# 2_bootleg-2-matrix.net
KiCad netlist of a schematic drawn in Altium Designer
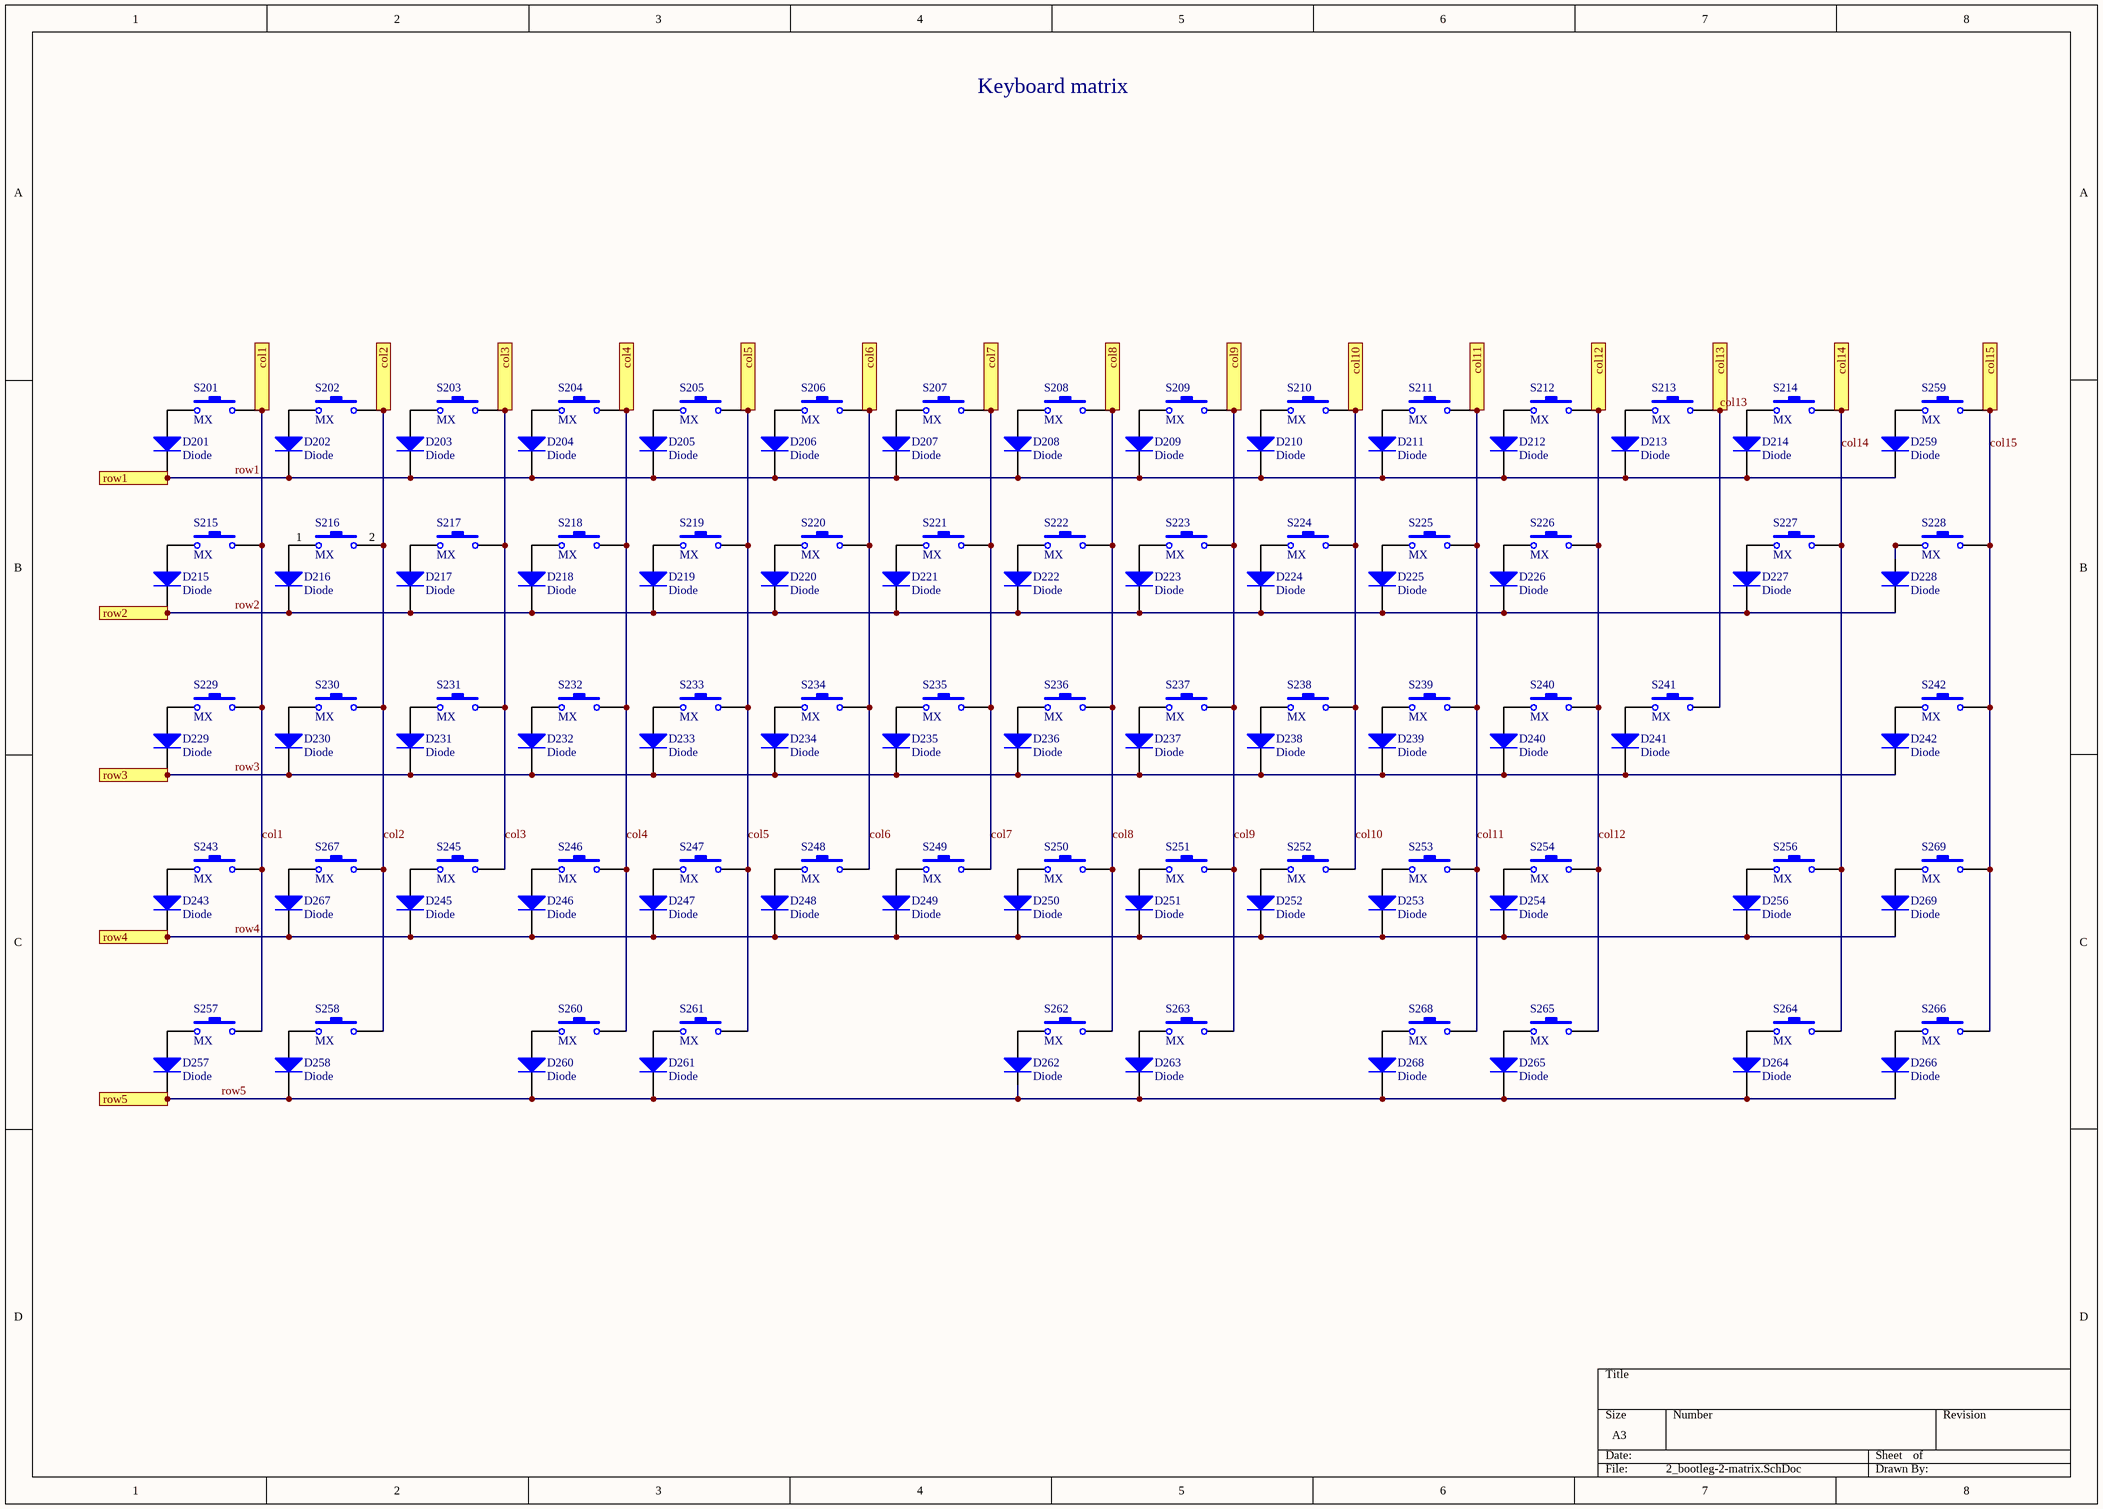
[diagram p0: 2_bootleg-2-matrix.SchDoc]

(export (version "E")
  (design (tool "Eeschema 10.0.6"))
  (components
    (comp (ref "D201")
      (value "Diode")
      (footprint "SOD-123")
      (description "Default Diode")
      (fields (field (name "MFG") "Bourns Inc.") (field (name "LCSC PART #") "C109002"))
      (libsource (lib "Miscellaneous Devices") (part "Diode"))
    )
    (comp (ref "D202")
      (value "Diode")
      (footprint "SOD-123")
      (description "Default Diode")
      (fields (field (name "MFG") "Bourns Inc.") (field (name "LCSC PART #") "C109002"))
      (libsource (lib "Miscellaneous Devices") (part "Diode"))
    )
    (comp (ref "D203")
      (value "Diode")
      (footprint "SOD-123")
      (description "Default Diode")
      (fields (field (name "MFG") "Bourns Inc.") (field (name "LCSC PART #") "C109002"))
      (libsource (lib "Miscellaneous Devices") (part "Diode"))
    )
    (comp (ref "D204")
      (value "Diode")
      (footprint "SOD-123")
      (description "Default Diode")
      (fields (field (name "MFG") "Bourns Inc.") (field (name "LCSC PART #") "C109002"))
      (libsource (lib "Miscellaneous Devices") (part "Diode"))
    )
    (comp (ref "D205")
      (value "Diode")
      (footprint "SOD-123")
      (description "Default Diode")
      (fields (field (name "MFG") "Bourns Inc.") (field (name "LCSC PART #") "C109002"))
      (libsource (lib "Miscellaneous Devices") (part "Diode"))
    )
    (comp (ref "D206")
      (value "Diode")
      (footprint "SOD-123")
      (description "Default Diode")
      (fields (field (name "MFG") "Bourns Inc.") (field (name "LCSC PART #") "C109002"))
      (libsource (lib "Miscellaneous Devices") (part "Diode"))
    )
    (comp (ref "D207")
      (value "Diode")
      (footprint "SOD-123")
      (description "Default Diode")
      (fields (field (name "MFG") "Bourns Inc.") (field (name "LCSC PART #") "C109002"))
      (libsource (lib "Miscellaneous Devices") (part "Diode"))
    )
    (comp (ref "D208")
      (value "Diode")
      (footprint "SOD-123")
      (description "Default Diode")
      (fields (field (name "MFG") "Bourns Inc.") (field (name "LCSC PART #") "C109002"))
      (libsource (lib "Miscellaneous Devices") (part "Diode"))
    )
    (comp (ref "D209")
      (value "Diode")
      (footprint "SOD-123")
      (description "Default Diode")
      (fields (field (name "MFG") "Bourns Inc.") (field (name "LCSC PART #") "C109002"))
      (libsource (lib "Miscellaneous Devices") (part "Diode"))
    )
    (comp (ref "D210")
      (value "Diode")
      (footprint "SOD-123")
      (description "Default Diode")
      (fields (field (name "MFG") "Bourns Inc.") (field (name "LCSC PART #") "C109002"))
      (libsource (lib "Miscellaneous Devices") (part "Diode"))
    )
    (comp (ref "D211")
      (value "Diode")
      (footprint "SOD-123")
      (description "Default Diode")
      (fields (field (name "MFG") "Bourns Inc.") (field (name "LCSC PART #") "C109002"))
      (libsource (lib "Miscellaneous Devices") (part "Diode"))
    )
    (comp (ref "D212")
      (value "Diode")
      (footprint "SOD-123")
      (description "Default Diode")
      (fields (field (name "MFG") "Bourns Inc.") (field (name "LCSC PART #") "C109002"))
      (libsource (lib "Miscellaneous Devices") (part "Diode"))
    )
    (comp (ref "D213")
      (value "Diode")
      (footprint "SOD-123")
      (description "Default Diode")
      (fields (field (name "MFG") "Bourns Inc.") (field (name "LCSC PART #") "C109002"))
      (libsource (lib "Miscellaneous Devices") (part "Diode"))
    )
    (comp (ref "D214")
      (value "Diode")
      (footprint "SOD-123")
      (description "Default Diode")
      (fields (field (name "MFG") "Bourns Inc.") (field (name "LCSC PART #") "C109002"))
      (libsource (lib "Miscellaneous Devices") (part "Diode"))
    )
    (comp (ref "D215")
      (value "Diode")
      (footprint "SOD-123")
      (description "Default Diode")
      (fields (field (name "MFG") "Bourns Inc.") (field (name "LCSC PART #") "C109002"))
      (libsource (lib "Miscellaneous Devices") (part "Diode"))
    )
    (comp (ref "D216")
      (value "Diode")
      (footprint "SOD-123")
      (description "Default Diode")
      (fields (field (name "MFG") "Bourns Inc.") (field (name "LCSC PART #") "C109002"))
      (libsource (lib "Miscellaneous Devices") (part "Diode"))
    )
    (comp (ref "D217")
      (value "Diode")
      (footprint "SOD-123")
      (description "Default Diode")
      (fields (field (name "MFG") "Bourns Inc.") (field (name "LCSC PART #") "C109002"))
      (libsource (lib "Miscellaneous Devices") (part "Diode"))
    )
    (comp (ref "D218")
      (value "Diode")
      (footprint "SOD-123")
      (description "Default Diode")
      (fields (field (name "MFG") "Bourns Inc.") (field (name "LCSC PART #") "C109002"))
      (libsource (lib "Miscellaneous Devices") (part "Diode"))
    )
    (comp (ref "D219")
      (value "Diode")
      (footprint "SOD-123")
      (description "Default Diode")
      (fields (field (name "MFG") "Bourns Inc.") (field (name "LCSC PART #") "C109002"))
      (libsource (lib "Miscellaneous Devices") (part "Diode"))
    )
    (comp (ref "D220")
      (value "Diode")
      (footprint "SOD-123")
      (description "Default Diode")
      (fields (field (name "MFG") "Bourns Inc.") (field (name "LCSC PART #") "C109002"))
      (libsource (lib "Miscellaneous Devices") (part "Diode"))
    )
    (comp (ref "D221")
      (value "Diode")
      (footprint "SOD-123")
      (description "Default Diode")
      (fields (field (name "MFG") "Bourns Inc.") (field (name "LCSC PART #") "C109002"))
      (libsource (lib "Miscellaneous Devices") (part "Diode"))
    )
    (comp (ref "D222")
      (value "Diode")
      (footprint "SOD-123")
      (description "Default Diode")
      (fields (field (name "MFG") "Bourns Inc.") (field (name "LCSC PART #") "C109002"))
      (libsource (lib "Miscellaneous Devices") (part "Diode"))
    )
    (comp (ref "D223")
      (value "Diode")
      (footprint "SOD-123")
      (description "Default Diode")
      (fields (field (name "MFG") "Bourns Inc.") (field (name "LCSC PART #") "C109002"))
      (libsource (lib "Miscellaneous Devices") (part "Diode"))
    )
    (comp (ref "D224")
      (value "Diode")
      (footprint "SOD-123")
      (description "Default Diode")
      (fields (field (name "MFG") "Bourns Inc.") (field (name "LCSC PART #") "C109002"))
      (libsource (lib "Miscellaneous Devices") (part "Diode"))
    )
    (comp (ref "D225")
      (value "Diode")
      (footprint "SOD-123")
      (description "Default Diode")
      (fields (field (name "MFG") "Bourns Inc.") (field (name "LCSC PART #") "C109002"))
      (libsource (lib "Miscellaneous Devices") (part "Diode"))
    )
    (comp (ref "D226")
      (value "Diode")
      (footprint "SOD-123")
      (description "Default Diode")
      (fields (field (name "MFG") "Bourns Inc.") (field (name "LCSC PART #") "C109002"))
      (libsource (lib "Miscellaneous Devices") (part "Diode"))
    )
    (comp (ref "D227")
      (value "Diode")
      (footprint "SOD-123")
      (description "Default Diode")
      (fields (field (name "MFG") "Bourns Inc.") (field (name "LCSC PART #") "C109002"))
      (libsource (lib "Miscellaneous Devices") (part "Diode"))
    )
    (comp (ref "D228")
      (value "Diode")
      (footprint "SOD-123")
      (description "Default Diode")
      (fields (field (name "MFG") "Bourns Inc.") (field (name "LCSC PART #") "C109002"))
      (libsource (lib "Miscellaneous Devices") (part "Diode"))
    )
    (comp (ref "D229")
      (value "Diode")
      (footprint "SOD-123")
      (description "Default Diode")
      (fields (field (name "MFG") "Bourns Inc.") (field (name "LCSC PART #") "C109002"))
      (libsource (lib "Miscellaneous Devices") (part "Diode"))
    )
    (comp (ref "D230")
      (value "Diode")
      (footprint "SOD-123")
      (description "Default Diode")
      (fields (field (name "MFG") "Bourns Inc.") (field (name "LCSC PART #") "C109002"))
      (libsource (lib "Miscellaneous Devices") (part "Diode"))
    )
    (comp (ref "D231")
      (value "Diode")
      (footprint "SOD-123")
      (description "Default Diode")
      (fields (field (name "MFG") "Bourns Inc.") (field (name "LCSC PART #") "C109002"))
      (libsource (lib "Miscellaneous Devices") (part "Diode"))
    )
    (comp (ref "D232")
      (value "Diode")
      (footprint "SOD-123")
      (description "Default Diode")
      (fields (field (name "MFG") "Bourns Inc.") (field (name "LCSC PART #") "C109002"))
      (libsource (lib "Miscellaneous Devices") (part "Diode"))
    )
    (comp (ref "D233")
      (value "Diode")
      (footprint "SOD-123")
      (description "Default Diode")
      (fields (field (name "MFG") "Bourns Inc.") (field (name "LCSC PART #") "C109002"))
      (libsource (lib "Miscellaneous Devices") (part "Diode"))
    )
    (comp (ref "D234")
      (value "Diode")
      (footprint "SOD-123")
      (description "Default Diode")
      (fields (field (name "MFG") "Bourns Inc.") (field (name "LCSC PART #") "C109002"))
      (libsource (lib "Miscellaneous Devices") (part "Diode"))
    )
    (comp (ref "D235")
      (value "Diode")
      (footprint "SOD-123")
      (description "Default Diode")
      (fields (field (name "MFG") "Bourns Inc.") (field (name "LCSC PART #") "C109002"))
      (libsource (lib "Miscellaneous Devices") (part "Diode"))
    )
    (comp (ref "D236")
      (value "Diode")
      (footprint "SOD-123")
      (description "Default Diode")
      (fields (field (name "MFG") "Bourns Inc.") (field (name "LCSC PART #") "C109002"))
      (libsource (lib "Miscellaneous Devices") (part "Diode"))
    )
    (comp (ref "D237")
      (value "Diode")
      (footprint "SOD-123")
      (description "Default Diode")
      (fields (field (name "MFG") "Bourns Inc.") (field (name "LCSC PART #") "C109002"))
      (libsource (lib "Miscellaneous Devices") (part "Diode"))
    )
    (comp (ref "D238")
      (value "Diode")
      (footprint "SOD-123")
      (description "Default Diode")
      (fields (field (name "MFG") "Bourns Inc.") (field (name "LCSC PART #") "C109002"))
      (libsource (lib "Miscellaneous Devices") (part "Diode"))
    )
    (comp (ref "D239")
      (value "Diode")
      (footprint "SOD-123")
      (description "Default Diode")
      (fields (field (name "MFG") "Bourns Inc.") (field (name "LCSC PART #") "C109002"))
      (libsource (lib "Miscellaneous Devices") (part "Diode"))
    )
    (comp (ref "D240")
      (value "Diode")
      (footprint "SOD-123")
      (description "Default Diode")
      (fields (field (name "MFG") "Bourns Inc.") (field (name "LCSC PART #") "C109002"))
      (libsource (lib "Miscellaneous Devices") (part "Diode"))
    )
    (comp (ref "D241")
      (value "Diode")
      (footprint "SOD-123")
      (description "Default Diode")
      (fields (field (name "MFG") "Bourns Inc.") (field (name "LCSC PART #") "C109002"))
      (libsource (lib "Miscellaneous Devices") (part "Diode"))
    )
    (comp (ref "D242")
      (value "Diode")
      (footprint "SOD-123")
      (description "Default Diode")
      (fields (field (name "MFG") "Bourns Inc.") (field (name "LCSC PART #") "C109002"))
      (libsource (lib "Miscellaneous Devices") (part "Diode"))
    )
    (comp (ref "D243")
      (value "Diode")
      (footprint "SOD-123")
      (description "Default Diode")
      (fields (field (name "MFG") "Bourns Inc.") (field (name "LCSC PART #") "C109002"))
      (libsource (lib "Miscellaneous Devices") (part "Diode"))
    )
    (comp (ref "D245")
      (value "Diode")
      (footprint "SOD-123")
      (description "Default Diode")
      (fields (field (name "MFG") "Bourns Inc.") (field (name "LCSC PART #") "C109002"))
      (libsource (lib "Miscellaneous Devices") (part "Diode"))
    )
    (comp (ref "D246")
      (value "Diode")
      (footprint "SOD-123")
      (description "Default Diode")
      (fields (field (name "MFG") "Bourns Inc.") (field (name "LCSC PART #") "C109002"))
      (libsource (lib "Miscellaneous Devices") (part "Diode"))
    )
    (comp (ref "D247")
      (value "Diode")
      (footprint "SOD-123")
      (description "Default Diode")
      (fields (field (name "MFG") "Bourns Inc.") (field (name "LCSC PART #") "C109002"))
      (libsource (lib "Miscellaneous Devices") (part "Diode"))
    )
    (comp (ref "D248")
      (value "Diode")
      (footprint "SOD-123")
      (description "Default Diode")
      (fields (field (name "MFG") "Bourns Inc.") (field (name "LCSC PART #") "C109002"))
      (libsource (lib "Miscellaneous Devices") (part "Diode"))
    )
    (comp (ref "D249")
      (value "Diode")
      (footprint "SOD-123")
      (description "Default Diode")
      (fields (field (name "MFG") "Bourns Inc.") (field (name "LCSC PART #") "C109002"))
      (libsource (lib "Miscellaneous Devices") (part "Diode"))
    )
    (comp (ref "D250")
      (value "Diode")
      (footprint "SOD-123")
      (description "Default Diode")
      (fields (field (name "MFG") "Bourns Inc.") (field (name "LCSC PART #") "C109002"))
      (libsource (lib "Miscellaneous Devices") (part "Diode"))
    )
    (comp (ref "D251")
      (value "Diode")
      (footprint "SOD-123")
      (description "Default Diode")
      (fields (field (name "MFG") "Bourns Inc.") (field (name "LCSC PART #") "C109002"))
      (libsource (lib "Miscellaneous Devices") (part "Diode"))
    )
    (comp (ref "D252")
      (value "Diode")
      (footprint "SOD-123")
      (description "Default Diode")
      (fields (field (name "MFG") "Bourns Inc.") (field (name "LCSC PART #") "C109002"))
      (libsource (lib "Miscellaneous Devices") (part "Diode"))
    )
    (comp (ref "D253")
      (value "Diode")
      (footprint "SOD-123")
      (description "Default Diode")
      (fields (field (name "MFG") "Bourns Inc.") (field (name "LCSC PART #") "C109002"))
      (libsource (lib "Miscellaneous Devices") (part "Diode"))
    )
    (comp (ref "D254")
      (value "Diode")
      (footprint "SOD-123")
      (description "Default Diode")
      (fields (field (name "MFG") "Bourns Inc.") (field (name "LCSC PART #") "C109002"))
      (libsource (lib "Miscellaneous Devices") (part "Diode"))
    )
    (comp (ref "D256")
      (value "Diode")
      (footprint "SOD-123")
      (description "Default Diode")
      (fields (field (name "MFG") "Bourns Inc.") (field (name "LCSC PART #") "C109002"))
      (libsource (lib "Miscellaneous Devices") (part "Diode"))
    )
    (comp (ref "D257")
      (value "Diode")
      (footprint "SOD-123")
      (description "Default Diode")
      (fields (field (name "MFG") "Bourns Inc.") (field (name "LCSC PART #") "C109002"))
      (libsource (lib "Miscellaneous Devices") (part "Diode"))
    )
    (comp (ref "D258")
      (value "Diode")
      (footprint "SOD-123")
      (description "Default Diode")
      (fields (field (name "MFG") "Bourns Inc.") (field (name "LCSC PART #") "C109002"))
      (libsource (lib "Miscellaneous Devices") (part "Diode"))
    )
    (comp (ref "D259")
      (value "Diode")
      (footprint "SOD-123")
      (description "Default Diode")
      (fields (field (name "MFG") "Bourns Inc.") (field (name "LCSC PART #") "C109002"))
      (libsource (lib "Miscellaneous Devices") (part "Diode"))
    )
    (comp (ref "D260")
      (value "Diode")
      (footprint "SOD-123")
      (description "Default Diode")
      (fields (field (name "MFG") "Bourns Inc.") (field (name "LCSC PART #") "C109002"))
      (libsource (lib "Miscellaneous Devices") (part "Diode"))
    )
    (comp (ref "D261")
      (value "Diode")
      (footprint "SOD-123")
      (description "Default Diode")
      (fields (field (name "MFG") "Bourns Inc.") (field (name "LCSC PART #") "C109002"))
      (libsource (lib "Miscellaneous Devices") (part "Diode"))
    )
    (comp (ref "D262")
      (value "Diode")
      (footprint "SOD-123")
      (description "Default Diode")
      (fields (field (name "MFG") "Bourns Inc.") (field (name "LCSC PART #") "C109002"))
      (libsource (lib "Miscellaneous Devices") (part "Diode"))
    )
    (comp (ref "D263")
      (value "Diode")
      (footprint "SOD-123")
      (description "Default Diode")
      (fields (field (name "MFG") "Bourns Inc.") (field (name "LCSC PART #") "C109002"))
      (libsource (lib "Miscellaneous Devices") (part "Diode"))
    )
    (comp (ref "D264")
      (value "Diode")
      (footprint "SOD-123")
      (description "Default Diode")
      (fields (field (name "MFG") "Bourns Inc.") (field (name "LCSC PART #") "C109002"))
      (libsource (lib "Miscellaneous Devices") (part "Diode"))
    )
    (comp (ref "D265")
      (value "Diode")
      (footprint "SOD-123")
      (description "Default Diode")
      (fields (field (name "MFG") "Bourns Inc.") (field (name "LCSC PART #") "C109002"))
      (libsource (lib "Miscellaneous Devices") (part "Diode"))
    )
    (comp (ref "D266")
      (value "Diode")
      (footprint "SOD-123")
      (description "Default Diode")
      (fields (field (name "MFG") "Bourns Inc.") (field (name "LCSC PART #") "C109002"))
      (libsource (lib "Miscellaneous Devices") (part "Diode"))
    )
    (comp (ref "D267")
      (value "Diode")
      (footprint "SOD-123")
      (description "Default Diode")
      (fields (field (name "MFG") "Bourns Inc.") (field (name "LCSC PART #") "C109002"))
      (libsource (lib "Miscellaneous Devices") (part "Diode"))
    )
    (comp (ref "D268")
      (value "Diode")
      (footprint "SOD-123")
      (description "Default Diode")
      (fields (field (name "MFG") "Bourns Inc.") (field (name "LCSC PART #") "C109002"))
      (libsource (lib "Miscellaneous Devices") (part "Diode"))
    )
    (comp (ref "D269")
      (value "Diode")
      (footprint "SOD-123")
      (description "Default Diode")
      (fields (field (name "MFG") "Bourns Inc.") (field (name "LCSC PART #") "C109002"))
      (libsource (lib "Miscellaneous Devices") (part "Diode"))
    )
    (comp (ref "S201")
      (value "MX")
      (footprint "Alps-switch - switched pol")
      (description "Switch")
      (libsource (lib "Miscellaneous Devices") (part "SW-PB"))
    )
    (comp (ref "S202")
      (value "MX")
      (footprint "Alps-switch - switched pol")
      (description "Switch")
      (libsource (lib "Miscellaneous Devices") (part "SW-PB"))
    )
    (comp (ref "S203")
      (value "MX")
      (footprint "Alps-switch - switched pol")
      (description "Switch")
      (libsource (lib "Miscellaneous Devices") (part "SW-PB"))
    )
    (comp (ref "S204")
      (value "MX")
      (footprint "Alps-switch - switched pol")
      (description "Switch")
      (libsource (lib "Miscellaneous Devices") (part "SW-PB"))
    )
    (comp (ref "S205")
      (value "MX")
      (footprint "Alps-switch - switched pol")
      (description "Switch")
      (libsource (lib "Miscellaneous Devices") (part "SW-PB"))
    )
    (comp (ref "S206")
      (value "MX")
      (footprint "Alps-switch - switched pol")
      (description "Switch")
      (libsource (lib "Miscellaneous Devices") (part "SW-PB"))
    )
    (comp (ref "S207")
      (value "MX")
      (footprint "Alps-switch - switched pol")
      (description "Switch")
      (libsource (lib "Miscellaneous Devices") (part "SW-PB"))
    )
    (comp (ref "S208")
      (value "MX")
      (footprint "Alps-switch - switched pol")
      (description "Switch")
      (libsource (lib "Miscellaneous Devices") (part "SW-PB"))
    )
    (comp (ref "S209")
      (value "MX")
      (footprint "Alps-switch - switched pol")
      (description "Switch")
      (libsource (lib "Miscellaneous Devices") (part "SW-PB"))
    )
    (comp (ref "S210")
      (value "MX")
      (footprint "Alps-switch - switched pol")
      (description "Switch")
      (libsource (lib "Miscellaneous Devices") (part "SW-PB"))
    )
    (comp (ref "S211")
      (value "MX")
      (footprint "Alps-switch - switched pol")
      (description "Switch")
      (libsource (lib "Miscellaneous Devices") (part "SW-PB"))
    )
    (comp (ref "S212")
      (value "MX")
      (footprint "Alps-switch - switched pol")
      (description "Switch")
      (libsource (lib "Miscellaneous Devices") (part "SW-PB"))
    )
    (comp (ref "S213")
      (value "MX")
      (footprint "Alps-switch - switched pol")
      (description "Switch")
      (libsource (lib "Miscellaneous Devices") (part "SW-PB"))
    )
    (comp (ref "S214")
      (value "MX")
      (footprint "Alps-switch - switched pol")
      (description "Switch")
      (libsource (lib "Miscellaneous Devices") (part "SW-PB"))
    )
    (comp (ref "S215")
      (value "MX")
      (footprint "ALPS-switch - 1.5U")
      (description "TAB")
      (libsource (lib "Miscellaneous Devices") (part "SW-PB"))
    )
    (comp (ref "S216")
      (value "MX")
      (footprint "Alps-switch - switched pol")
      (description "Switch")
      (libsource (lib "") (part "SW-PB_1"))
    )
    (comp (ref "S217")
      (value "MX")
      (footprint "Alps-switch - switched pol")
      (description "Switch")
      (libsource (lib "Miscellaneous Devices") (part "SW-PB"))
    )
    (comp (ref "S218")
      (value "MX")
      (footprint "Alps-switch - switched pol")
      (description "Switch")
      (libsource (lib "Miscellaneous Devices") (part "SW-PB"))
    )
    (comp (ref "S219")
      (value "MX")
      (footprint "Alps-switch - switched pol")
      (description "Switch")
      (libsource (lib "Miscellaneous Devices") (part "SW-PB"))
    )
    (comp (ref "S220")
      (value "MX")
      (footprint "Alps-switch - switched pol")
      (description "Switch")
      (libsource (lib "Miscellaneous Devices") (part "SW-PB"))
    )
    (comp (ref "S221")
      (value "MX")
      (footprint "Alps-switch - switched pol")
      (description "Switch")
      (libsource (lib "Miscellaneous Devices") (part "SW-PB"))
    )
    (comp (ref "S222")
      (value "MX")
      (footprint "Alps-switch - switched pol")
      (description "Switch")
      (libsource (lib "Miscellaneous Devices") (part "SW-PB"))
    )
    (comp (ref "S223")
      (value "MX")
      (footprint "Alps-switch - switched pol")
      (description "Switch")
      (libsource (lib "Miscellaneous Devices") (part "SW-PB"))
    )
    (comp (ref "S224")
      (value "MX")
      (footprint "Alps-switch - switched pol")
      (description "Switch")
      (libsource (lib "Miscellaneous Devices") (part "SW-PB"))
    )
    (comp (ref "S225")
      (value "MX")
      (footprint "Alps-switch - switched pol")
      (description "Switch")
      (libsource (lib "Miscellaneous Devices") (part "SW-PB"))
    )
    (comp (ref "S226")
      (value "MX")
      (footprint "Alps-switch")
      (description "Switch")
      (libsource (lib "Miscellaneous Devices") (part "SW-PB"))
    )
    (comp (ref "S227")
      (value "MX")
      (footprint "Alps-switch - switched pol")
      (description "Switch")
      (libsource (lib "Miscellaneous Devices") (part "SW-PB"))
    )
    (comp (ref "S228")
      (value "MX")
      (footprint "ALPS-switch - 1.5U")
      (description "Switch")
      (libsource (lib "Miscellaneous Devices") (part "SW-PB"))
    )
    (comp (ref "S229")
      (value "MX")
      (footprint "ALPS-switch - CAPS")
      (description "Switch")
      (libsource (lib "Miscellaneous Devices") (part "SW-PB"))
    )
    (comp (ref "S230")
      (value "MX")
      (footprint "Alps-switch - switched pol")
      (description "Switch")
      (libsource (lib "Miscellaneous Devices") (part "SW-PB"))
    )
    (comp (ref "S231")
      (value "MX")
      (footprint "Alps-switch - switched pol")
      (description "Switch")
      (libsource (lib "Miscellaneous Devices") (part "SW-PB"))
    )
    (comp (ref "S232")
      (value "MX")
      (footprint "Alps-switch - switched pol")
      (description "Switch")
      (libsource (lib "Miscellaneous Devices") (part "SW-PB"))
    )
    (comp (ref "S233")
      (value "MX")
      (footprint "Alps-switch - switched pol")
      (description "Switch")
      (libsource (lib "Miscellaneous Devices") (part "SW-PB"))
    )
    (comp (ref "S234")
      (value "MX")
      (footprint "Alps-switch - switched pol")
      (description "Switch")
      (libsource (lib "Miscellaneous Devices") (part "SW-PB"))
    )
    (comp (ref "S235")
      (value "MX")
      (footprint "Alps-switch - switched pol")
      (description "Switch")
      (libsource (lib "Miscellaneous Devices") (part "SW-PB"))
    )
    (comp (ref "S236")
      (value "MX")
      (footprint "Alps-switch - switched pol")
      (description "Switch")
      (libsource (lib "Miscellaneous Devices") (part "SW-PB"))
    )
    (comp (ref "S237")
      (value "MX")
      (footprint "Alps-switch - switched pol")
      (description "Switch")
      (libsource (lib "Miscellaneous Devices") (part "SW-PB"))
    )
    (comp (ref "S238")
      (value "MX")
      (footprint "Alps-switch - switched pol")
      (description "Switch")
      (libsource (lib "Miscellaneous Devices") (part "SW-PB"))
    )
    (comp (ref "S239")
      (value "MX")
      (footprint "Alps-switch")
      (description "Switch")
      (libsource (lib "Miscellaneous Devices") (part "SW-PB"))
    )
    (comp (ref "S240")
      (value "MX")
      (footprint "Alps-switch - switched pol")
      (description "Switch")
      (libsource (lib "Miscellaneous Devices") (part "SW-PB"))
    )
    (comp (ref "S241")
      (value "MX")
      (footprint "Alps-switch")
      (description "Switch")
      (libsource (lib "Miscellaneous Devices") (part "SW-PB"))
    )
    (comp (ref "S242")
      (value "MX")
      (footprint "ALPS-switch - Enter")
      (description "Switch")
      (libsource (lib "Miscellaneous Devices") (part "SW-PB"))
    )
    (comp (ref "S243")
      (value "MX")
      (footprint "ALPS-switch - Left shift v2")
      (description "Switch")
      (libsource (lib "Miscellaneous Devices") (part "SW-PB"))
    )
    (comp (ref "S245")
      (value "MX")
      (footprint "Alps-switch - switched pol")
      (description "Switch")
      (libsource (lib "Miscellaneous Devices") (part "SW-PB"))
    )
    (comp (ref "S246")
      (value "MX")
      (footprint "Alps-switch - switched pol")
      (description "Switch")
      (libsource (lib "Miscellaneous Devices") (part "SW-PB"))
    )
    (comp (ref "S247")
      (value "MX")
      (footprint "Alps-switch - switched pol")
      (description "Switch")
      (libsource (lib "Miscellaneous Devices") (part "SW-PB"))
    )
    (comp (ref "S248")
      (value "MX")
      (footprint "Alps-switch - switched pol")
      (description "Switch")
      (libsource (lib "Miscellaneous Devices") (part "SW-PB"))
    )
    (comp (ref "S249")
      (value "MX")
      (footprint "Alps-switch - switched pol")
      (description "Switch")
      (libsource (lib "Miscellaneous Devices") (part "SW-PB"))
    )
    (comp (ref "S250")
      (value "MX")
      (footprint "Alps-switch - switched pol")
      (description "Switch")
      (libsource (lib "Miscellaneous Devices") (part "SW-PB"))
    )
    (comp (ref "S251")
      (value "MX")
      (footprint "Alps-switch - switched pol")
      (description "Switch")
      (libsource (lib "Miscellaneous Devices") (part "SW-PB"))
    )
    (comp (ref "S252")
      (value "MX")
      (footprint "Alps-switch - switched pol")
      (description "Switch")
      (libsource (lib "Miscellaneous Devices") (part "SW-PB"))
    )
    (comp (ref "S253")
      (value "MX")
      (footprint "Alps-switch - switched pol")
      (description "Switch")
      (libsource (lib "Miscellaneous Devices") (part "SW-PB"))
    )
    (comp (ref "S254")
      (value "MX")
      (footprint "Alps-switch - switched pol")
      (description "Switch")
      (libsource (lib "Miscellaneous Devices") (part "SW-PB"))
    )
    (comp (ref "S256")
      (value "MX")
      (footprint "ALPS-switch - right shift - stabs")
      (description "Switch")
      (libsource (lib "Miscellaneous Devices") (part "SW-PB"))
    )
    (comp (ref "S257")
      (value "MX")
      (footprint "ALPS-switch - 1.5u MOD-L")
      (description "Switch")
      (libsource (lib "Miscellaneous Devices") (part "SW-PB"))
    )
    (comp (ref "S258")
      (value "MX")
      (footprint "ALPS-switch - L_WIN - AEKISO60")
      (description "Switch")
      (libsource (lib "Miscellaneous Devices") (part "SW-PB"))
    )
    (comp (ref "S259")
      (value "MX")
      (footprint "ALPS-switch - backspace")
      (description "Switch")
      (libsource (lib "Miscellaneous Devices") (part "SW-PB"))
    )
    (comp (ref "S260")
      (value "MX")
      (footprint "ALPS-switch - L_alt - V2")
      (description "Switch")
      (libsource (lib "Miscellaneous Devices") (part "SW-PB"))
    )
    (comp (ref "S261")
      (value "MX")
      (footprint "ALPS-SWITCH - L SPLIT SPACE_V2")
      (description "Switch")
      (libsource (lib "Miscellaneous Devices") (part "SW-PB"))
    )
    (comp (ref "S262")
      (value "MX")
      (footprint "ALPS-switch - Space_V3")
      (description "Switch")
      (libsource (lib "Miscellaneous Devices") (part "SW-PB"))
    )
    (comp (ref "S263")
      (value "MX")
      (footprint "ALPS-SWITCH - R SPLIT SPACE_V2")
      (description "Switch")
      (libsource (lib "Miscellaneous Devices") (part "SW-PB"))
    )
    (comp (ref "S264")
      (value "MX")
      (footprint "ALPS-switch - R_WIN - AEKISO60")
      (description "Switch")
      (libsource (lib "Miscellaneous Devices") (part "SW-PB"))
    )
    (comp (ref "S265")
      (value "MX")
      (footprint "ALPS-switch - R_alt - V2")
      (description "Switch")
      (libsource (lib "Miscellaneous Devices") (part "SW-PB"))
    )
    (comp (ref "S266")
      (value "MX")
      (footprint "ALPS-switch - 1.5u MOD-R")
      (description "Switch")
      (libsource (lib "Miscellaneous Devices") (part "SW-PB"))
    )
    (comp (ref "S267")
      (value "MX")
      (footprint "Alps-switch - switched pol")
      (description "Switch")
      (libsource (lib "Miscellaneous Devices") (part "SW-PB"))
    )
    (comp (ref "S268")
      (value "MX")
      (footprint "Alps-switch - switched pol")
      (description "Switch")
      (libsource (lib "Miscellaneous Devices") (part "SW-PB"))
    )
    (comp (ref "S269")
      (value "MX")
      (footprint "Alps-switch")
      (description "Switch")
      (libsource (lib "Miscellaneous Devices") (part "SW-PB"))
    )
  )
  (nets
    (net (code "1") (name "/col1") (class "Default")
      (node (ref "S201") (pin "2") (pinfunction "2_2") (pintype "passive"))
      (node (ref "S215") (pin "2") (pinfunction "2_2") (pintype "passive"))
      (node (ref "S229") (pin "2") (pinfunction "2_2") (pintype "passive"))
      (node (ref "S243") (pin "1") (pinfunction "1_1") (pintype "passive"))
      (node (ref "S257") (pin "1") (pinfunction "1_1") (pintype "passive"))
    )
    (net (code "2") (name "/col2") (class "Default")
      (node (ref "S202") (pin "2") (pinfunction "2_2") (pintype "passive"))
      (node (ref "S216") (pin "2") (pinfunction "2_2") (pintype "passive"))
      (node (ref "S230") (pin "2") (pinfunction "2_2") (pintype "passive"))
      (node (ref "S258") (pin "2") (pinfunction "2_2") (pintype "passive"))
      (node (ref "S267") (pin "2") (pinfunction "2_2") (pintype "passive"))
    )
    (net (code "3") (name "/col3") (class "Default")
      (node (ref "S203") (pin "2") (pinfunction "2_2") (pintype "passive"))
      (node (ref "S217") (pin "2") (pinfunction "2_2") (pintype "passive"))
      (node (ref "S231") (pin "2") (pinfunction "2_2") (pintype "passive"))
      (node (ref "S245") (pin "2") (pinfunction "2_2") (pintype "passive"))
    )
    (net (code "4") (name "/col4") (class "Default")
      (node (ref "S204") (pin "2") (pinfunction "2_2") (pintype "passive"))
      (node (ref "S218") (pin "2") (pinfunction "2_2") (pintype "passive"))
      (node (ref "S232") (pin "2") (pinfunction "2_2") (pintype "passive"))
      (node (ref "S246") (pin "2") (pinfunction "2_2") (pintype "passive"))
      (node (ref "S260") (pin "2") (pinfunction "2_2") (pintype "passive"))
    )
    (net (code "5") (name "/col5") (class "Default")
      (node (ref "S205") (pin "2") (pinfunction "2_2") (pintype "passive"))
      (node (ref "S219") (pin "2") (pinfunction "2_2") (pintype "passive"))
      (node (ref "S233") (pin "2") (pinfunction "2_2") (pintype "passive"))
      (node (ref "S247") (pin "2") (pinfunction "2_2") (pintype "passive"))
      (node (ref "S261") (pin "2") (pinfunction "2_2") (pintype "passive"))
    )
    (net (code "6") (name "/col6") (class "Default")
      (node (ref "S206") (pin "2") (pinfunction "2_2") (pintype "passive"))
      (node (ref "S220") (pin "2") (pinfunction "2_2") (pintype "passive"))
      (node (ref "S234") (pin "2") (pinfunction "2_2") (pintype "passive"))
      (node (ref "S248") (pin "2") (pinfunction "2_2") (pintype "passive"))
    )
    (net (code "7") (name "/col7") (class "Default")
      (node (ref "S207") (pin "2") (pinfunction "2_2") (pintype "passive"))
      (node (ref "S221") (pin "2") (pinfunction "2_2") (pintype "passive"))
      (node (ref "S235") (pin "2") (pinfunction "2_2") (pintype "passive"))
      (node (ref "S249") (pin "2") (pinfunction "2_2") (pintype "passive"))
    )
    (net (code "8") (name "/col8") (class "Default")
      (node (ref "S208") (pin "2") (pinfunction "2_2") (pintype "passive"))
      (node (ref "S222") (pin "2") (pinfunction "2_2") (pintype "passive"))
      (node (ref "S236") (pin "2") (pinfunction "2_2") (pintype "passive"))
      (node (ref "S250") (pin "2") (pinfunction "2_2") (pintype "passive"))
      (node (ref "S262") (pin "2") (pinfunction "2_2") (pintype "passive"))
    )
    (net (code "9") (name "/col9") (class "Default")
      (node (ref "S209") (pin "2") (pinfunction "2_2") (pintype "passive"))
      (node (ref "S223") (pin "2") (pinfunction "2_2") (pintype "passive"))
      (node (ref "S237") (pin "2") (pinfunction "2_2") (pintype "passive"))
      (node (ref "S251") (pin "2") (pinfunction "2_2") (pintype "passive"))
      (node (ref "S263") (pin "2") (pinfunction "2_2") (pintype "passive"))
    )
    (net (code "10") (name "/col10") (class "Default")
      (node (ref "S210") (pin "2") (pinfunction "2_2") (pintype "passive"))
      (node (ref "S224") (pin "2") (pinfunction "2_2") (pintype "passive"))
      (node (ref "S238") (pin "2") (pinfunction "2_2") (pintype "passive"))
      (node (ref "S252") (pin "2") (pinfunction "2_2") (pintype "passive"))
    )
    (net (code "11") (name "/col11") (class "Default")
      (node (ref "S211") (pin "2") (pinfunction "2_2") (pintype "passive"))
      (node (ref "S225") (pin "2") (pinfunction "2_2") (pintype "passive"))
      (node (ref "S239") (pin "2") (pinfunction "2_2") (pintype "passive"))
      (node (ref "S253") (pin "2") (pinfunction "2_2") (pintype "passive"))
      (node (ref "S268") (pin "1") (pinfunction "1_1") (pintype "passive"))
    )
    (net (code "12") (name "/col12") (class "Default")
      (node (ref "S212") (pin "2") (pinfunction "2_2") (pintype "passive"))
      (node (ref "S226") (pin "2") (pinfunction "2_2") (pintype "passive"))
      (node (ref "S240") (pin "2") (pinfunction "2_2") (pintype "passive"))
      (node (ref "S254") (pin "2") (pinfunction "2_2") (pintype "passive"))
      (node (ref "S265") (pin "2") (pinfunction "2_2") (pintype "passive"))
    )
    (net (code "13") (name "/col13") (class "Default")
      (node (ref "S213") (pin "2") (pinfunction "2_2") (pintype "passive"))
      (node (ref "S241") (pin "2") (pinfunction "2_2") (pintype "passive"))
    )
    (net (code "14") (name "/col14") (class "Default")
      (node (ref "S214") (pin "2") (pinfunction "2_2") (pintype "passive"))
      (node (ref "S227") (pin "2") (pinfunction "2_2") (pintype "passive"))
      (node (ref "S256") (pin "1") (pinfunction "1_1") (pintype "passive"))
      (node (ref "S264") (pin "2") (pinfunction "2_2") (pintype "passive"))
    )
    (net (code "15") (name "/col15") (class "Default")
      (node (ref "S228") (pin "2") (pinfunction "2_2") (pintype "passive"))
      (node (ref "S242") (pin "1") (pinfunction "1_1") (pintype "passive"))
      (node (ref "S259") (pin "2") (pinfunction "2_2") (pintype "passive"))
      (node (ref "S266") (pin "2") (pinfunction "2_2") (pintype "passive"))
      (node (ref "S269") (pin "2") (pinfunction "2_2") (pintype "passive"))
    )
    (net (code "16") (name "/row1") (class "Default")
      (node (ref "D201") (pin "2") (pinfunction "K_2") (pintype "passive"))
      (node (ref "D202") (pin "2") (pinfunction "K_2") (pintype "passive"))
      (node (ref "D203") (pin "2") (pinfunction "K_2") (pintype "passive"))
      (node (ref "D204") (pin "2") (pinfunction "K_2") (pintype "passive"))
      (node (ref "D205") (pin "2") (pinfunction "K_2") (pintype "passive"))
      (node (ref "D206") (pin "2") (pinfunction "K_2") (pintype "passive"))
      (node (ref "D207") (pin "2") (pinfunction "K_2") (pintype "passive"))
      (node (ref "D208") (pin "2") (pinfunction "K_2") (pintype "passive"))
      (node (ref "D209") (pin "2") (pinfunction "K_2") (pintype "passive"))
      (node (ref "D210") (pin "2") (pinfunction "K_2") (pintype "passive"))
      (node (ref "D211") (pin "2") (pinfunction "K_2") (pintype "passive"))
      (node (ref "D212") (pin "2") (pinfunction "K_2") (pintype "passive"))
      (node (ref "D213") (pin "2") (pinfunction "K_2") (pintype "passive"))
      (node (ref "D214") (pin "2") (pinfunction "K_2") (pintype "passive"))
      (node (ref "D259") (pin "2") (pinfunction "K_2") (pintype "passive"))
    )
    (net (code "17") (name "/row2") (class "Default")
      (node (ref "D215") (pin "2") (pinfunction "K_2") (pintype "passive"))
      (node (ref "D216") (pin "2") (pinfunction "K_2") (pintype "passive"))
      (node (ref "D217") (pin "2") (pinfunction "K_2") (pintype "passive"))
      (node (ref "D218") (pin "2") (pinfunction "K_2") (pintype "passive"))
      (node (ref "D219") (pin "2") (pinfunction "K_2") (pintype "passive"))
      (node (ref "D220") (pin "2") (pinfunction "K_2") (pintype "passive"))
      (node (ref "D221") (pin "2") (pinfunction "K_2") (pintype "passive"))
      (node (ref "D222") (pin "2") (pinfunction "K_2") (pintype "passive"))
      (node (ref "D223") (pin "2") (pinfunction "K_2") (pintype "passive"))
      (node (ref "D224") (pin "2") (pinfunction "K_2") (pintype "passive"))
      (node (ref "D225") (pin "2") (pinfunction "K_2") (pintype "passive"))
      (node (ref "D226") (pin "2") (pinfunction "K_2") (pintype "passive"))
      (node (ref "D227") (pin "2") (pinfunction "K_2") (pintype "passive"))
      (node (ref "D228") (pin "2") (pinfunction "K_2") (pintype "passive"))
    )
    (net (code "18") (name "/row3") (class "Default")
      (node (ref "D229") (pin "2") (pinfunction "K_2") (pintype "passive"))
      (node (ref "D230") (pin "2") (pinfunction "K_2") (pintype "passive"))
      (node (ref "D231") (pin "2") (pinfunction "K_2") (pintype "passive"))
      (node (ref "D232") (pin "2") (pinfunction "K_2") (pintype "passive"))
      (node (ref "D233") (pin "2") (pinfunction "K_2") (pintype "passive"))
      (node (ref "D234") (pin "2") (pinfunction "K_2") (pintype "passive"))
      (node (ref "D235") (pin "2") (pinfunction "K_2") (pintype "passive"))
      (node (ref "D236") (pin "2") (pinfunction "K_2") (pintype "passive"))
      (node (ref "D237") (pin "2") (pinfunction "K_2") (pintype "passive"))
      (node (ref "D238") (pin "2") (pinfunction "K_2") (pintype "passive"))
      (node (ref "D239") (pin "2") (pinfunction "K_2") (pintype "passive"))
      (node (ref "D240") (pin "2") (pinfunction "K_2") (pintype "passive"))
      (node (ref "D241") (pin "2") (pinfunction "K_2") (pintype "passive"))
      (node (ref "D242") (pin "2") (pinfunction "K_2") (pintype "passive"))
    )
    (net (code "19") (name "/row4") (class "Default")
      (node (ref "D243") (pin "2") (pinfunction "K_2") (pintype "passive"))
      (node (ref "D245") (pin "2") (pinfunction "K_2") (pintype "passive"))
      (node (ref "D246") (pin "2") (pinfunction "K_2") (pintype "passive"))
      (node (ref "D247") (pin "2") (pinfunction "K_2") (pintype "passive"))
      (node (ref "D248") (pin "2") (pinfunction "K_2") (pintype "passive"))
      (node (ref "D249") (pin "2") (pinfunction "K_2") (pintype "passive"))
      (node (ref "D250") (pin "2") (pinfunction "K_2") (pintype "passive"))
      (node (ref "D251") (pin "2") (pinfunction "K_2") (pintype "passive"))
      (node (ref "D252") (pin "2") (pinfunction "K_2") (pintype "passive"))
      (node (ref "D253") (pin "2") (pinfunction "K_2") (pintype "passive"))
      (node (ref "D254") (pin "2") (pinfunction "K_2") (pintype "passive"))
      (node (ref "D256") (pin "2") (pinfunction "K_2") (pintype "passive"))
      (node (ref "D267") (pin "2") (pinfunction "K_2") (pintype "passive"))
      (node (ref "D269") (pin "2") (pinfunction "K_2") (pintype "passive"))
    )
    (net (code "20") (name "/row5") (class "Default")
      (node (ref "D257") (pin "2") (pinfunction "K_2") (pintype "passive"))
      (node (ref "D258") (pin "2") (pinfunction "K_2") (pintype "passive"))
      (node (ref "D260") (pin "2") (pinfunction "K_2") (pintype "passive"))
      (node (ref "D261") (pin "2") (pinfunction "K_2") (pintype "passive"))
      (node (ref "D262") (pin "2") (pinfunction "K_2") (pintype "passive"))
      (node (ref "D263") (pin "2") (pinfunction "K_2") (pintype "passive"))
      (node (ref "D264") (pin "2") (pinfunction "K_2") (pintype "passive"))
      (node (ref "D265") (pin "2") (pinfunction "K_2") (pintype "passive"))
      (node (ref "D266") (pin "2") (pinfunction "K_2") (pintype "passive"))
      (node (ref "D268") (pin "2") (pinfunction "K_2") (pintype "passive"))
    )
    (net (code "21") (name "Net-(D201-A)") (class "Default")
      (node (ref "D201") (pin "1") (pinfunction "A_1") (pintype "passive"))
      (node (ref "S201") (pin "1") (pinfunction "1_1") (pintype "passive"))
    )
    (net (code "22") (name "Net-(D202-A)") (class "Default")
      (node (ref "D202") (pin "1") (pinfunction "A_1") (pintype "passive"))
      (node (ref "S202") (pin "1") (pinfunction "1_1") (pintype "passive"))
    )
    (net (code "23") (name "Net-(D203-A)") (class "Default")
      (node (ref "D203") (pin "1") (pinfunction "A_1") (pintype "passive"))
      (node (ref "S203") (pin "1") (pinfunction "1_1") (pintype "passive"))
    )
    (net (code "24") (name "Net-(D204-A)") (class "Default")
      (node (ref "D204") (pin "1") (pinfunction "A_1") (pintype "passive"))
      (node (ref "S204") (pin "1") (pinfunction "1_1") (pintype "passive"))
    )
    (net (code "25") (name "Net-(D205-A)") (class "Default")
      (node (ref "D205") (pin "1") (pinfunction "A_1") (pintype "passive"))
      (node (ref "S205") (pin "1") (pinfunction "1_1") (pintype "passive"))
    )
    (net (code "26") (name "Net-(D206-A)") (class "Default")
      (node (ref "D206") (pin "1") (pinfunction "A_1") (pintype "passive"))
      (node (ref "S206") (pin "1") (pinfunction "1_1") (pintype "passive"))
    )
    (net (code "27") (name "Net-(D207-A)") (class "Default")
      (node (ref "D207") (pin "1") (pinfunction "A_1") (pintype "passive"))
      (node (ref "S207") (pin "1") (pinfunction "1_1") (pintype "passive"))
    )
    (net (code "28") (name "Net-(D208-A)") (class "Default")
      (node (ref "D208") (pin "1") (pinfunction "A_1") (pintype "passive"))
      (node (ref "S208") (pin "1") (pinfunction "1_1") (pintype "passive"))
    )
    (net (code "29") (name "Net-(D209-A)") (class "Default")
      (node (ref "D209") (pin "1") (pinfunction "A_1") (pintype "passive"))
      (node (ref "S209") (pin "1") (pinfunction "1_1") (pintype "passive"))
    )
    (net (code "30") (name "Net-(D210-A)") (class "Default")
      (node (ref "D210") (pin "1") (pinfunction "A_1") (pintype "passive"))
      (node (ref "S210") (pin "1") (pinfunction "1_1") (pintype "passive"))
    )
    (net (code "31") (name "Net-(D211-A)") (class "Default")
      (node (ref "D211") (pin "1") (pinfunction "A_1") (pintype "passive"))
      (node (ref "S211") (pin "1") (pinfunction "1_1") (pintype "passive"))
    )
    (net (code "32") (name "Net-(D212-A)") (class "Default")
      (node (ref "D212") (pin "1") (pinfunction "A_1") (pintype "passive"))
      (node (ref "S212") (pin "1") (pinfunction "1_1") (pintype "passive"))
    )
    (net (code "33") (name "Net-(D213-A)") (class "Default")
      (node (ref "D213") (pin "1") (pinfunction "A_1") (pintype "passive"))
      (node (ref "S213") (pin "1") (pinfunction "1_1") (pintype "passive"))
    )
    (net (code "34") (name "Net-(D214-A)") (class "Default")
      (node (ref "D214") (pin "1") (pinfunction "A_1") (pintype "passive"))
      (node (ref "S214") (pin "1") (pinfunction "1_1") (pintype "passive"))
    )
    (net (code "35") (name "Net-(D215-A)") (class "Default")
      (node (ref "D215") (pin "1") (pinfunction "A_1") (pintype "passive"))
      (node (ref "S215") (pin "1") (pinfunction "1_1") (pintype "passive"))
    )
    (net (code "36") (name "Net-(D216-A)") (class "Default")
      (node (ref "D216") (pin "1") (pinfunction "A_1") (pintype "passive"))
      (node (ref "S216") (pin "1") (pinfunction "1_1") (pintype "passive"))
    )
    (net (code "37") (name "Net-(D217-A)") (class "Default")
      (node (ref "D217") (pin "1") (pinfunction "A_1") (pintype "passive"))
      (node (ref "S217") (pin "1") (pinfunction "1_1") (pintype "passive"))
    )
    (net (code "38") (name "Net-(D218-A)") (class "Default")
      (node (ref "D218") (pin "1") (pinfunction "A_1") (pintype "passive"))
      (node (ref "S218") (pin "1") (pinfunction "1_1") (pintype "passive"))
    )
    (net (code "39") (name "Net-(D219-A)") (class "Default")
      (node (ref "D219") (pin "1") (pinfunction "A_1") (pintype "passive"))
      (node (ref "S219") (pin "1") (pinfunction "1_1") (pintype "passive"))
    )
    (net (code "40") (name "Net-(D220-A)") (class "Default")
      (node (ref "D220") (pin "1") (pinfunction "A_1") (pintype "passive"))
      (node (ref "S220") (pin "1") (pinfunction "1_1") (pintype "passive"))
    )
    (net (code "41") (name "Net-(D221-A)") (class "Default")
      (node (ref "D221") (pin "1") (pinfunction "A_1") (pintype "passive"))
      (node (ref "S221") (pin "1") (pinfunction "1_1") (pintype "passive"))
    )
    (net (code "42") (name "Net-(D222-A)") (class "Default")
      (node (ref "D222") (pin "1") (pinfunction "A_1") (pintype "passive"))
      (node (ref "S222") (pin "1") (pinfunction "1_1") (pintype "passive"))
    )
    (net (code "43") (name "Net-(D223-A)") (class "Default")
      (node (ref "D223") (pin "1") (pinfunction "A_1") (pintype "passive"))
      (node (ref "S223") (pin "1") (pinfunction "1_1") (pintype "passive"))
    )
    (net (code "44") (name "Net-(D224-A)") (class "Default")
      (node (ref "D224") (pin "1") (pinfunction "A_1") (pintype "passive"))
      (node (ref "S224") (pin "1") (pinfunction "1_1") (pintype "passive"))
    )
    (net (code "45") (name "Net-(D225-A)") (class "Default")
      (node (ref "D225") (pin "1") (pinfunction "A_1") (pintype "passive"))
      (node (ref "S225") (pin "1") (pinfunction "1_1") (pintype "passive"))
    )
    (net (code "46") (name "Net-(D226-A)") (class "Default")
      (node (ref "D226") (pin "1") (pinfunction "A_1") (pintype "passive"))
      (node (ref "S226") (pin "1") (pinfunction "1_1") (pintype "passive"))
    )
    (net (code "47") (name "Net-(D227-A)") (class "Default")
      (node (ref "D227") (pin "1") (pinfunction "A_1") (pintype "passive"))
      (node (ref "S227") (pin "1") (pinfunction "1_1") (pintype "passive"))
    )
    (net (code "48") (name "Net-(D228-A)") (class "Default")
      (node (ref "D228") (pin "1") (pinfunction "A_1") (pintype "passive"))
      (node (ref "S228") (pin "1") (pinfunction "1_1") (pintype "passive"))
    )
    (net (code "49") (name "Net-(D229-A)") (class "Default")
      (node (ref "D229") (pin "1") (pinfunction "A_1") (pintype "passive"))
      (node (ref "S229") (pin "1") (pinfunction "1_1") (pintype "passive"))
    )
    (net (code "50") (name "Net-(D230-A)") (class "Default")
      (node (ref "D230") (pin "1") (pinfunction "A_1") (pintype "passive"))
      (node (ref "S230") (pin "1") (pinfunction "1_1") (pintype "passive"))
    )
    (net (code "51") (name "Net-(D231-A)") (class "Default")
      (node (ref "D231") (pin "1") (pinfunction "A_1") (pintype "passive"))
      (node (ref "S231") (pin "1") (pinfunction "1_1") (pintype "passive"))
    )
    (net (code "52") (name "Net-(D232-A)") (class "Default")
      (node (ref "D232") (pin "1") (pinfunction "A_1") (pintype "passive"))
      (node (ref "S232") (pin "1") (pinfunction "1_1") (pintype "passive"))
    )
    (net (code "53") (name "Net-(D233-A)") (class "Default")
      (node (ref "D233") (pin "1") (pinfunction "A_1") (pintype "passive"))
      (node (ref "S233") (pin "1") (pinfunction "1_1") (pintype "passive"))
    )
    (net (code "54") (name "Net-(D234-A)") (class "Default")
      (node (ref "D234") (pin "1") (pinfunction "A_1") (pintype "passive"))
      (node (ref "S234") (pin "1") (pinfunction "1_1") (pintype "passive"))
    )
    (net (code "55") (name "Net-(D235-A)") (class "Default")
      (node (ref "D235") (pin "1") (pinfunction "A_1") (pintype "passive"))
      (node (ref "S235") (pin "1") (pinfunction "1_1") (pintype "passive"))
    )
    (net (code "56") (name "Net-(D236-A)") (class "Default")
      (node (ref "D236") (pin "1") (pinfunction "A_1") (pintype "passive"))
      (node (ref "S236") (pin "1") (pinfunction "1_1") (pintype "passive"))
    )
    (net (code "57") (name "Net-(D237-A)") (class "Default")
      (node (ref "D237") (pin "1") (pinfunction "A_1") (pintype "passive"))
      (node (ref "S237") (pin "1") (pinfunction "1_1") (pintype "passive"))
    )
    (net (code "58") (name "Net-(D238-A)") (class "Default")
      (node (ref "D238") (pin "1") (pinfunction "A_1") (pintype "passive"))
      (node (ref "S238") (pin "1") (pinfunction "1_1") (pintype "passive"))
    )
    (net (code "59") (name "Net-(D239-A)") (class "Default")
      (node (ref "D239") (pin "1") (pinfunction "A_1") (pintype "passive"))
      (node (ref "S239") (pin "1") (pinfunction "1_1") (pintype "passive"))
    )
    (net (code "60") (name "Net-(D240-A)") (class "Default")
      (node (ref "D240") (pin "1") (pinfunction "A_1") (pintype "passive"))
      (node (ref "S240") (pin "1") (pinfunction "1_1") (pintype "passive"))
    )
    (net (code "61") (name "Net-(D241-A)") (class "Default")
      (node (ref "D241") (pin "1") (pinfunction "A_1") (pintype "passive"))
      (node (ref "S241") (pin "1") (pinfunction "1_1") (pintype "passive"))
    )
    (net (code "62") (name "Net-(D242-A)") (class "Default")
      (node (ref "D242") (pin "1") (pinfunction "A_1") (pintype "passive"))
      (node (ref "S242") (pin "2") (pinfunction "2_2") (pintype "passive"))
    )
    (net (code "63") (name "Net-(D243-A)") (class "Default")
      (node (ref "D243") (pin "1") (pinfunction "A_1") (pintype "passive"))
      (node (ref "S243") (pin "2") (pinfunction "2_2") (pintype "passive"))
    )
    (net (code "64") (name "Net-(D245-A)") (class "Default")
      (node (ref "D245") (pin "1") (pinfunction "A_1") (pintype "passive"))
      (node (ref "S245") (pin "1") (pinfunction "1_1") (pintype "passive"))
    )
    (net (code "65") (name "Net-(D246-A)") (class "Default")
      (node (ref "D246") (pin "1") (pinfunction "A_1") (pintype "passive"))
      (node (ref "S246") (pin "1") (pinfunction "1_1") (pintype "passive"))
    )
    (net (code "66") (name "Net-(D247-A)") (class "Default")
      (node (ref "D247") (pin "1") (pinfunction "A_1") (pintype "passive"))
      (node (ref "S247") (pin "1") (pinfunction "1_1") (pintype "passive"))
    )
    (net (code "67") (name "Net-(D248-A)") (class "Default")
      (node (ref "D248") (pin "1") (pinfunction "A_1") (pintype "passive"))
      (node (ref "S248") (pin "1") (pinfunction "1_1") (pintype "passive"))
    )
    (net (code "68") (name "Net-(D249-A)") (class "Default")
      (node (ref "D249") (pin "1") (pinfunction "A_1") (pintype "passive"))
      (node (ref "S249") (pin "1") (pinfunction "1_1") (pintype "passive"))
    )
    (net (code "69") (name "Net-(D250-A)") (class "Default")
      (node (ref "D250") (pin "1") (pinfunction "A_1") (pintype "passive"))
      (node (ref "S250") (pin "1") (pinfunction "1_1") (pintype "passive"))
    )
    (net (code "70") (name "Net-(D251-A)") (class "Default")
      (node (ref "D251") (pin "1") (pinfunction "A_1") (pintype "passive"))
      (node (ref "S251") (pin "1") (pinfunction "1_1") (pintype "passive"))
    )
    (net (code "71") (name "Net-(D252-A)") (class "Default")
      (node (ref "D252") (pin "1") (pinfunction "A_1") (pintype "passive"))
      (node (ref "S252") (pin "1") (pinfunction "1_1") (pintype "passive"))
    )
    (net (code "72") (name "Net-(D253-A)") (class "Default")
      (node (ref "D253") (pin "1") (pinfunction "A_1") (pintype "passive"))
      (node (ref "S253") (pin "1") (pinfunction "1_1") (pintype "passive"))
    )
    (net (code "73") (name "Net-(D254-A)") (class "Default")
      (node (ref "D254") (pin "1") (pinfunction "A_1") (pintype "passive"))
      (node (ref "S254") (pin "1") (pinfunction "1_1") (pintype "passive"))
    )
    (net (code "74") (name "Net-(D256-A)") (class "Default")
      (node (ref "D256") (pin "1") (pinfunction "A_1") (pintype "passive"))
      (node (ref "S256") (pin "2") (pinfunction "2_2") (pintype "passive"))
    )
    (net (code "75") (name "Net-(D257-A)") (class "Default")
      (node (ref "D257") (pin "1") (pinfunction "A_1") (pintype "passive"))
      (node (ref "S257") (pin "2") (pinfunction "2_2") (pintype "passive"))
    )
    (net (code "76") (name "Net-(D258-A)") (class "Default")
      (node (ref "D258") (pin "1") (pinfunction "A_1") (pintype "passive"))
      (node (ref "S258") (pin "1") (pinfunction "1_1") (pintype "passive"))
    )
    (net (code "77") (name "Net-(D259-A)") (class "Default")
      (node (ref "D259") (pin "1") (pinfunction "A_1") (pintype "passive"))
      (node (ref "S259") (pin "1") (pinfunction "1_1") (pintype "passive"))
    )
    (net (code "78") (name "Net-(D260-A)") (class "Default")
      (node (ref "D260") (pin "1") (pinfunction "A_1") (pintype "passive"))
      (node (ref "S260") (pin "1") (pinfunction "1_1") (pintype "passive"))
    )
    (net (code "79") (name "Net-(D261-A)") (class "Default")
      (node (ref "D261") (pin "1") (pinfunction "A_1") (pintype "passive"))
      (node (ref "S261") (pin "1") (pinfunction "1_1") (pintype "passive"))
    )
    (net (code "80") (name "Net-(D262-A)") (class "Default")
      (node (ref "D262") (pin "1") (pinfunction "A_1") (pintype "passive"))
      (node (ref "S262") (pin "1") (pinfunction "1_1") (pintype "passive"))
    )
    (net (code "81") (name "Net-(D263-A)") (class "Default")
      (node (ref "D263") (pin "1") (pinfunction "A_1") (pintype "passive"))
      (node (ref "S263") (pin "1") (pinfunction "1_1") (pintype "passive"))
    )
    (net (code "82") (name "Net-(D264-A)") (class "Default")
      (node (ref "D264") (pin "1") (pinfunction "A_1") (pintype "passive"))
      (node (ref "S264") (pin "1") (pinfunction "1_1") (pintype "passive"))
    )
    (net (code "83") (name "Net-(D265-A)") (class "Default")
      (node (ref "D265") (pin "1") (pinfunction "A_1") (pintype "passive"))
      (node (ref "S265") (pin "1") (pinfunction "1_1") (pintype "passive"))
    )
    (net (code "84") (name "Net-(D266-A)") (class "Default")
      (node (ref "D266") (pin "1") (pinfunction "A_1") (pintype "passive"))
      (node (ref "S266") (pin "1") (pinfunction "1_1") (pintype "passive"))
    )
    (net (code "85") (name "Net-(D267-A)") (class "Default")
      (node (ref "D267") (pin "1") (pinfunction "A_1") (pintype "passive"))
      (node (ref "S267") (pin "1") (pinfunction "1_1") (pintype "passive"))
    )
    (net (code "86") (name "Net-(D268-A)") (class "Default")
      (node (ref "D268") (pin "1") (pinfunction "A_1") (pintype "passive"))
      (node (ref "S268") (pin "2") (pinfunction "2_2") (pintype "passive"))
    )
    (net (code "87") (name "Net-(D269-A)") (class "Default")
      (node (ref "D269") (pin "1") (pinfunction "A_1") (pintype "passive"))
      (node (ref "S269") (pin "1") (pinfunction "1_1") (pintype "passive"))
    )
  )
)
